# dhunter_bike_texted.net
KiCad netlist of a schematic drawn in EAGLE
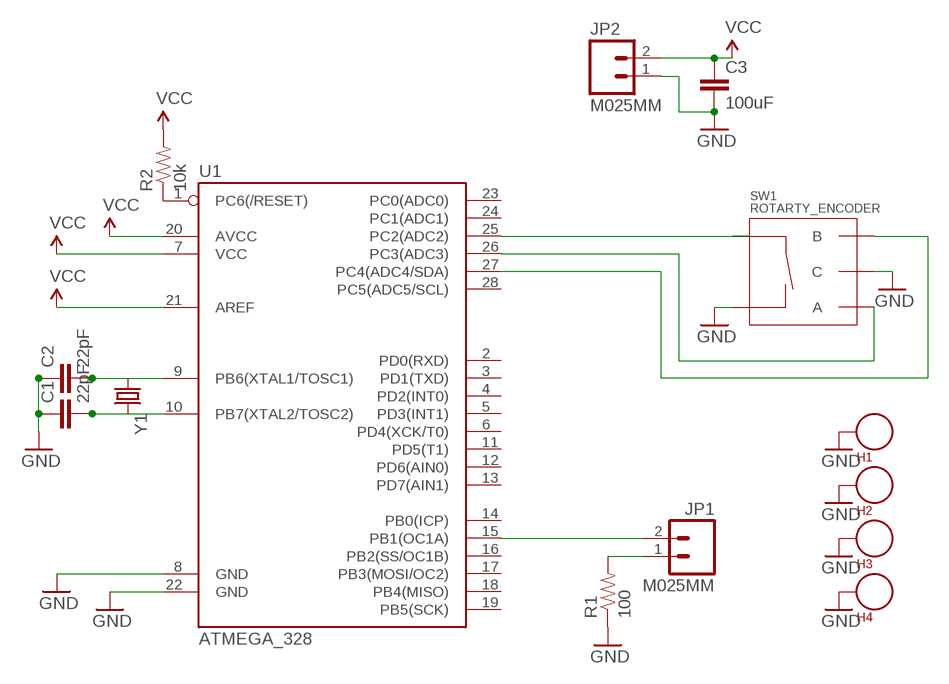
[diagram p0: schematic, sheet 1]

(export (version "E")
  (design (tool "Eeschema 10.0.6"))
  (components
    (comp (ref "C1")
      (value "22pF")
      (footprint "eagle-import:CAP-PTH-SMALLEZ")
      (libsource (lib "eagle-import") (part "CAPEZ"))
    )
    (comp (ref "C2")
      (value "22pF")
      (footprint "eagle-import:CAP-PTH-SMALLEZ")
      (libsource (lib "eagle-import") (part "CAPEZ"))
    )
    (comp (ref "C3")
      (value "100uF")
      (footprint "eagle-import:CAP-PTH-SMALLEZ")
      (libsource (lib "eagle-import") (part "CAPEZ"))
    )
    (comp (ref "H1")
      (value "SEW_HOLE")
      (footprint "eagle-import:SIMPLE_HOLE")
      (libsource (lib "eagle-import") (part "SEW_HOLE"))
    )
    (comp (ref "H2")
      (value "SEW_HOLE")
      (footprint "eagle-import:SIMPLE_HOLE")
      (libsource (lib "eagle-import") (part "SEW_HOLE"))
    )
    (comp (ref "H3")
      (value "SEW_HOLE")
      (footprint "eagle-import:SIMPLE_HOLE")
      (libsource (lib "eagle-import") (part "SEW_HOLE"))
    )
    (comp (ref "H4")
      (value "SEW_HOLE")
      (footprint "eagle-import:SIMPLE_HOLE")
      (libsource (lib "eagle-import") (part "SEW_HOLE"))
    )
    (comp (ref "JP1")
      (value "M025MM")
      (footprint "eagle-import:SCREWTERMINAL-5MM-2")
      (libsource (lib "eagle-import") (part "M025MM"))
    )
    (comp (ref "JP2")
      (value "M025MM")
      (footprint "eagle-import:SCREWTERMINAL-5MM-2")
      (libsource (lib "eagle-import") (part "M025MM"))
    )
    (comp (ref "R1")
      (value "100")
      (footprint "eagle-import:AXIAL-0.3EZ")
      (libsource (lib "eagle-import") (part "RESISTOREZ"))
    )
    (comp (ref "R2")
      (value "10k")
      (footprint "eagle-import:AXIAL-0.3EZ")
      (libsource (lib "eagle-import") (part "RESISTOREZ"))
    )
    (comp (ref "SW1")
      (value "ROTARTY_ENCODER")
      (footprint "eagle-import:ROTARY_ENC_PLAIN")
      (libsource (lib "eagle-import") (part "ROTARTY_ENCODER"))
    )
    (comp (ref "U1")
      (value "ATMEGA_328")
      (footprint "eagle-import:DIL28-3")
      (libsource (lib "eagle-import") (part "ATMEGA328P_PDIP"))
    )
    (comp (ref "Y1")
      (value "CRYSTALHC49US")
      (footprint "eagle-import:HC49US")
      (libsource (lib "eagle-import") (part "CRYSTALHC49US"))
    )
  )
  (nets
    (net (code "1") (name "GND") (class "Default")
      (node (ref "C1") (pin "1") (pinfunction "1_1") (pintype "passive"))
      (node (ref "C2") (pin "1") (pinfunction "1_1") (pintype "passive"))
      (node (ref "C3") (pin "2") (pinfunction "2_2") (pintype "passive"))
      (node (ref "H1") (pin "P$1") (pinfunction "P$1_P$1") (pintype "bidirectional"))
      (node (ref "H2") (pin "P$1") (pinfunction "P$1_P$1") (pintype "bidirectional"))
      (node (ref "H3") (pin "P$1") (pinfunction "P$1_P$1") (pintype "bidirectional"))
      (node (ref "H4") (pin "P$1") (pinfunction "P$1_P$1") (pintype "bidirectional"))
      (node (ref "JP2") (pin "1") (pinfunction "1_1") (pintype "passive"))
      (node (ref "R1") (pin "P$1") (pinfunction "1_P$1") (pintype "passive"))
      (node (ref "SW1") (pin "C") (pinfunction "C_C") (pintype "bidirectional"))
      (node (ref "SW1") (pin "SW-") (pinfunction "SW-_SW-") (pintype "bidirectional"))
      (node (ref "U1") (pin "22") (pinfunction "GND_22") (pintype "bidirectional"))
      (node (ref "U1") (pin "8") (pinfunction "GND_8") (pintype "bidirectional"))
    )
    (net (code "2") (name "Net-(R1-2)") (class "Default")
      (node (ref "JP1") (pin "1") (pinfunction "1_1") (pintype "passive"))
      (node (ref "R1") (pin "P$2") (pinfunction "2_P$2") (pintype "passive"))
    )
    (net (code "3") (name "Net-(R2-1)") (class "Default")
      (node (ref "R2") (pin "P$1") (pinfunction "1_P$1") (pintype "passive"))
      (node (ref "U1") (pin "1") (pinfunction "PC6(/RESET)_1") (pintype "bidirectional"))
    )
    (net (code "4") (name "Net-(U1-PB1(OC1A))") (class "Default")
      (node (ref "JP1") (pin "2") (pinfunction "2_2") (pintype "passive"))
      (node (ref "U1") (pin "15") (pinfunction "PB1(OC1A)_15") (pintype "bidirectional"))
    )
    (net (code "5") (name "Net-(U1-PB6(XTAL1{slash}TOSC1))") (class "Default")
      (node (ref "C2") (pin "2") (pinfunction "2_2") (pintype "passive"))
      (node (ref "U1") (pin "9") (pinfunction "PB6(XTAL1/TOSC1)_9") (pintype "bidirectional"))
      (node (ref "Y1") (pin "1") (pinfunction "1_1") (pintype "passive"))
    )
    (net (code "6") (name "Net-(U1-PB7(XTAL2{slash}TOSC2))") (class "Default")
      (node (ref "C1") (pin "2") (pinfunction "2_2") (pintype "passive"))
      (node (ref "U1") (pin "10") (pinfunction "PB7(XTAL2/TOSC2)_10") (pintype "bidirectional"))
      (node (ref "Y1") (pin "2") (pinfunction "2_2") (pintype "passive"))
    )
    (net (code "7") (name "Net-(U1-PC2(ADC2))") (class "Default")
      (node (ref "SW1") (pin "SW+") (pinfunction "SW+_SW+") (pintype "bidirectional"))
      (node (ref "U1") (pin "25") (pinfunction "PC2(ADC2)_25") (pintype "bidirectional"))
    )
    (net (code "8") (name "Net-(U1-PC3(ADC3))") (class "Default")
      (node (ref "SW1") (pin "A") (pinfunction "A_A") (pintype "bidirectional"))
      (node (ref "U1") (pin "26") (pinfunction "PC3(ADC3)_26") (pintype "bidirectional"))
    )
    (net (code "9") (name "Net-(U1-PC4(ADC4{slash}SDA))") (class "Default")
      (node (ref "SW1") (pin "B") (pinfunction "B_B") (pintype "bidirectional"))
      (node (ref "U1") (pin "27") (pinfunction "PC4(ADC4/SDA)_27") (pintype "bidirectional"))
    )
    (net (code "10") (name "VCC") (class "Default")
      (node (ref "C3") (pin "1") (pinfunction "1_1") (pintype "passive"))
      (node (ref "JP2") (pin "2") (pinfunction "2_2") (pintype "passive"))
      (node (ref "R2") (pin "P$2") (pinfunction "2_P$2") (pintype "passive"))
      (node (ref "U1") (pin "20") (pinfunction "AVCC_20") (pintype "bidirectional"))
      (node (ref "U1") (pin "21") (pinfunction "AREF_21") (pintype "bidirectional"))
      (node (ref "U1") (pin "7") (pinfunction "VCC_7") (pintype "bidirectional"))
    )
    (net (code "11") (name "unconnected-(U1-PB0(ICP)-Pad14)") (class "Default")
      (node (ref "U1") (pin "14") (pinfunction "PB0(ICP)_14") (pintype "bidirectional"))
    )
    (net (code "12") (name "unconnected-(U1-PB2(SS{slash}OC1B)-Pad16)") (class "Default")
      (node (ref "U1") (pin "16") (pinfunction "PB2(SS/OC1B)_16") (pintype "bidirectional"))
    )
    (net (code "13") (name "unconnected-(U1-PB3(MOSI{slash}OC2)-Pad17)") (class "Default")
      (node (ref "U1") (pin "17") (pinfunction "PB3(MOSI/OC2)_17") (pintype "bidirectional"))
    )
    (net (code "14") (name "unconnected-(U1-PB4(MISO)-Pad18)") (class "Default")
      (node (ref "U1") (pin "18") (pinfunction "PB4(MISO)_18") (pintype "bidirectional"))
    )
    (net (code "15") (name "unconnected-(U1-PB5(SCK)-Pad19)") (class "Default")
      (node (ref "U1") (pin "19") (pinfunction "PB5(SCK)_19") (pintype "bidirectional"))
    )
    (net (code "16") (name "unconnected-(U1-PC0(ADC0)-Pad23)") (class "Default")
      (node (ref "U1") (pin "23") (pinfunction "PC0(ADC0)_23") (pintype "bidirectional"))
    )
    (net (code "17") (name "unconnected-(U1-PC1(ADC1)-Pad24)") (class "Default")
      (node (ref "U1") (pin "24") (pinfunction "PC1(ADC1)_24") (pintype "bidirectional"))
    )
    (net (code "18") (name "unconnected-(U1-PC5(ADC5{slash}SCL)-Pad28)") (class "Default")
      (node (ref "U1") (pin "28") (pinfunction "PC5(ADC5/SCL)_28") (pintype "bidirectional"))
    )
    (net (code "19") (name "unconnected-(U1-PD0(RXD)-Pad2)") (class "Default")
      (node (ref "U1") (pin "2") (pinfunction "PD0(RXD)_2") (pintype "bidirectional"))
    )
    (net (code "20") (name "unconnected-(U1-PD1(TXD)-Pad3)") (class "Default")
      (node (ref "U1") (pin "3") (pinfunction "PD1(TXD)_3") (pintype "bidirectional"))
    )
    (net (code "21") (name "unconnected-(U1-PD2(INT0)-Pad4)") (class "Default")
      (node (ref "U1") (pin "4") (pinfunction "PD2(INT0)_4") (pintype "bidirectional"))
    )
    (net (code "22") (name "unconnected-(U1-PD3(INT1)-Pad5)") (class "Default")
      (node (ref "U1") (pin "5") (pinfunction "PD3(INT1)_5") (pintype "bidirectional"))
    )
    (net (code "23") (name "unconnected-(U1-PD4(XCK{slash}T0)-Pad6)") (class "Default")
      (node (ref "U1") (pin "6") (pinfunction "PD4(XCK/T0)_6") (pintype "bidirectional"))
    )
    (net (code "24") (name "unconnected-(U1-PD5(T1)-Pad11)") (class "Default")
      (node (ref "U1") (pin "11") (pinfunction "PD5(T1)_11") (pintype "bidirectional"))
    )
    (net (code "25") (name "unconnected-(U1-PD6(AIN0)-Pad12)") (class "Default")
      (node (ref "U1") (pin "12") (pinfunction "PD6(AIN0)_12") (pintype "bidirectional"))
    )
    (net (code "26") (name "unconnected-(U1-PD7(AIN1)-Pad13)") (class "Default")
      (node (ref "U1") (pin "13") (pinfunction "PD7(AIN1)_13") (pintype "bidirectional"))
    )
  )
)
